# Encoder_Sheet3.net
KiCad netlist of a schematic drawn in Altium Designer
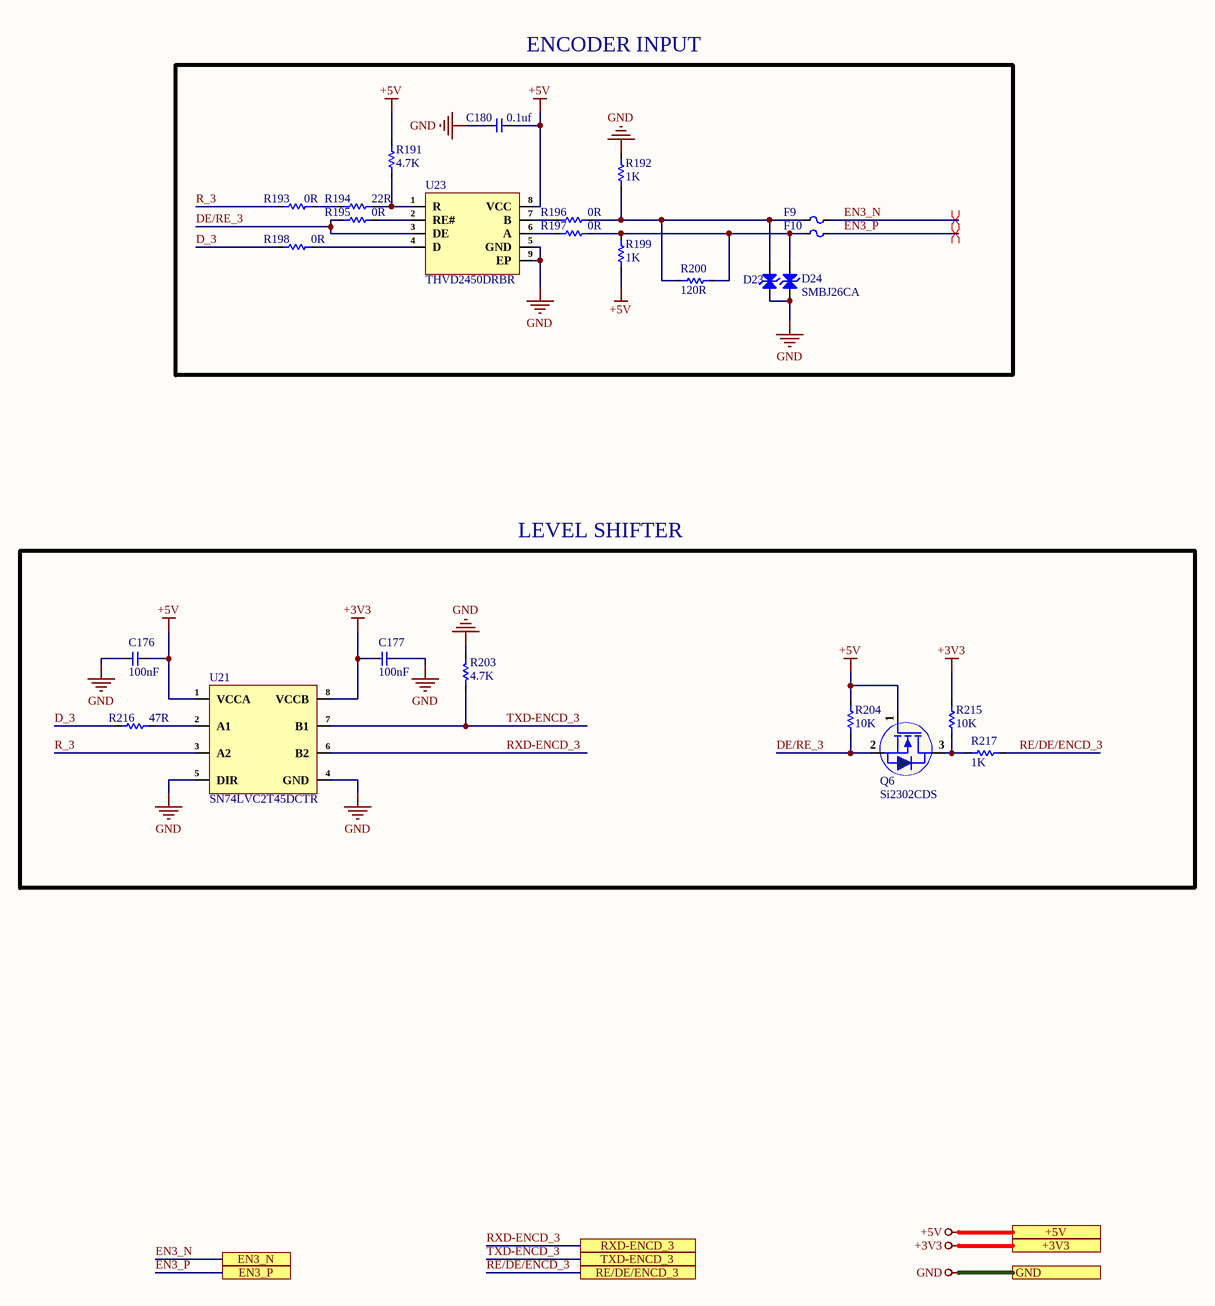
[diagram p0: Encoder_Sheet3.SchDoc]

(export (version "E")
  (design (tool "Eeschema 10.0.6"))
  (components
    (comp (ref "C176")
      (value "100nF")
      (footprint "cap-0402")
      (description "CAP CER 0.1UF 50V X7R 0402")
      (fields
        (field (name "MANUFACTURER") "TDK")
        (field (name "MANUFACTURER PART NUMBER") "C1005X7R1H104KT000F")
      )
      (libsource (lib "eSpark Libraries") (part "C1005X7R1H104KT000F"))
    )
    (comp (ref "C177")
      (value "100nF")
      (footprint "cap-0402")
      (description "CAP CER 0.1UF 50V X7R 0402")
      (fields
        (field (name "MANUFACTURER") "TDK")
        (field (name "MANUFACTURER PART NUMBER") "C1005X7R1H104KT000F")
      )
      (libsource (lib "eSpark Libraries") (part "C1005X7R1H104KT000F"))
    )
    (comp (ref "C180")
      (value "0.1uf")
      (footprint "Cap-0402")
      (description "CAP CER 0.1UF 100V X5R 0402")
      (fields
        (field (name "MANUFACTURER") "Murata")
        (field (name "MANUFACTURER PART NUMBER") "GRM155R62A104KE14D")
      )
      (libsource (lib "eSpark Libraries") (part "GRM155R62A104KE14D"))
    )
    (comp (ref "D23")
      (value "SMBJ26CA")
      (footprint "SMB Bi Directional")
      (description "SMB(DO-214AA) TVS ROHS")
      (fields (field (name "MANUFACTURER") "MSKSEMI") (field (name "LCSC PART NUMBER") "C5331111"))
      (libsource (lib "eSpark Libraries") (part "SMBJ26CA"))
    )
    (comp (ref "D24")
      (value "SMBJ26CA")
      (footprint "SMB Bi Directional")
      (description "SMB(DO-214AA) TVS ROHS")
      (fields (field (name "MANUFACTURER") "MSKSEMI") (field (name "LCSC PART NUMBER") "C5331111"))
      (libsource (lib "eSpark Libraries") (part "SMBJ26CA"))
    )
    (comp (ref "F9")
      (value "SMD0805P020TF")
      (footprint "Fuse-0805")
      (description "9V 200mA 100A 500mA 0805 Resettable Fuses ROHS")
      (fields (field (name "MANUFACTURER") "RUILON") (field (name "LCSC PART NUMBER") "C20976"))
      (libsource (lib "eSpark_centralized_Library(2022)") (part "SMD0805P020TF"))
    )
    (comp (ref "F10")
      (value "SMD0805P020TF")
      (footprint "Fuse-0805")
      (description "9V 200mA 100A 500mA 0805 Resettable Fuses ROHS")
      (fields (field (name "MANUFACTURER") "RUILON") (field (name "LCSC PART NUMBER") "C20976"))
      (libsource (lib "eSpark_centralized_Library(2022)") (part "SMD0805P020TF"))
    )
    (comp (ref "Q6")
      (value "Si2302CDS")
      (footprint "Sot-23")
      (description "N-CHANNEL 20-V (D-S) MOSFET")
      (fields
        (field (name "MANUFACTURER") "TECH PUBLIC")
        (field (name "MANUFACTURER PART NUMBER") "SI2302CDS")
      )
      (libsource (lib "eSpark_centralized_Library(2022)") (part "Si2302CDS"))
    )
    (comp (ref "R191")
      (value "4.7K")
      (footprint "Res-0402")
      (description "RES 4.7K OHM 1% 1/16W 0402")
      (fields
        (field (name "MANUFACTURER") "Yageo")
        (field (name "MANUFACTURER PART NUMBER") "RC0402FR-074K7L")
      )
      (libsource (lib "eSpark Libraries") (part "RC0402FR-074K7L"))
    )
    (comp (ref "R192")
      (value "1K")
      (footprint "Res-0402")
      (description "RES 1K OHM 1% 1/16W 0402")
      (fields
        (field (name "MANUFACTURER") "Yageo")
        (field (name "MANUFACTURER PART NUMBER") "RC0402FR-071KL")
      )
      (libsource (lib "eSpark Libraries") (part "RC0402FR-071KL"))
    )
    (comp (ref "R193")
      (value "0R")
      (footprint "Res-0603")
      (description "RES 0 OHM JUMPER 1/10W 0603")
      (fields
        (field (name "MANUFACTURER") "Yageo")
        (field (name "MANUFACTURER PART NUMBER") "RC0603JR-070RL")
      )
      (libsource (lib "eSpark Libraries") (part "RC0603JR-070RL"))
    )
    (comp (ref "R194")
      (value "22R")
      (footprint "Res-0402")
      (description "RES 22 OHM 1% 1/16W 0402")
      (fields
        (field (name "MANUFACTURER") "Yageo")
        (field (name "MANUFACTURER PART NUMBER") "RC0402FR-0722RL")
      )
      (libsource (lib "eSpark Libraries") (part "RC0402FR-0722RL"))
    )
    (comp (ref "R195")
      (value "0R")
      (footprint "Res-0603")
      (description "RES 0 OHM JUMPER 1/10W 0603")
      (fields
        (field (name "MANUFACTURER") "Yageo")
        (field (name "MANUFACTURER PART NUMBER") "RC0603JR-070RL")
      )
      (libsource (lib "eSpark Libraries") (part "RC0603JR-070RL"))
    )
    (comp (ref "R196")
      (value "0R")
      (footprint "Res-0603")
      (description "RES 0 OHM JUMPER 1/10W 0603")
      (fields
        (field (name "MANUFACTURER") "Yageo")
        (field (name "MANUFACTURER PART NUMBER") "RC0603JR-070RL")
      )
      (libsource (lib "eSpark Libraries") (part "RC0603JR-070RL"))
    )
    (comp (ref "R197")
      (value "0R")
      (footprint "Res-0603")
      (description "RES 0 OHM JUMPER 1/10W 0603")
      (fields
        (field (name "MANUFACTURER") "Yageo")
        (field (name "MANUFACTURER PART NUMBER") "RC0603JR-070RL")
      )
      (libsource (lib "eSpark Libraries") (part "RC0603JR-070RL"))
    )
    (comp (ref "R198")
      (value "0R")
      (footprint "Res-0603")
      (description "RES 0 OHM JUMPER 1/10W 0603")
      (fields
        (field (name "MANUFACTURER") "Yageo")
        (field (name "MANUFACTURER PART NUMBER") "RC0603JR-070RL")
      )
      (libsource (lib "eSpark Libraries") (part "RC0603JR-070RL"))
    )
    (comp (ref "R199")
      (value "1K")
      (footprint "Res-0402")
      (description "RES 1K OHM 1% 1/16W 0402")
      (fields
        (field (name "MANUFACTURER") "Yageo")
        (field (name "MANUFACTURER PART NUMBER") "RC0402FR-071KL")
      )
      (libsource (lib "eSpark Libraries") (part "RC0402FR-071KL"))
    )
    (comp (ref "R200")
      (value "120R")
      (footprint "Res-0402")
      (description "RES 120 OHM 1% 1/16W 0402")
      (fields
        (field (name "MANUFACTURER") "Yageo")
        (field (name "MANUFACTURER PART NUMBER") "RC0402FR-07120RL")
      )
      (libsource (lib "eSpark Libraries") (part "RC0402FR-07120RL"))
    )
    (comp (ref "R203")
      (value "4.7K")
      (footprint "Res-0402")
      (description "RES 4.7K OHM 1% 1/16W 0402")
      (fields
        (field (name "MANUFACTURER") "Yageo")
        (field (name "MANUFACTURER PART NUMBER") "RC0402FR-074K7L")
      )
      (libsource (lib "eSpark Libraries") (part "RC0402FR-074K7L"))
    )
    (comp (ref "R204")
      (value "10K")
      (footprint "Res-0402")
      (description "RES 10K OHM 1% 1/16W 0402")
      (fields
        (field (name "MANUFACTURER") "Yageo")
        (field (name "MANUFACTURER PART NUMBER") "RC0402FR-0710KL")
      )
      (libsource (lib "eSpark_centralized_Library(2022)") (part "RC0402FR-0710KL"))
    )
    (comp (ref "R215")
      (value "10K")
      (footprint "Res-0402")
      (description "RES 10K OHM 1% 1/16W 0402")
      (fields
        (field (name "MANUFACTURER") "Yageo")
        (field (name "MANUFACTURER PART NUMBER") "RC0402FR-0710KL")
      )
      (libsource (lib "eSpark_centralized_Library(2022)") (part "RC0402FR-0710KL"))
    )
    (comp (ref "R216")
      (value "47R")
      (footprint "Res-0402")
      (description "RES 47 OHM 1% 1/16W 0402")
      (fields
        (field (name "MANUFACTURER") "Yageo")
        (field (name "MANUFACTURER PART NUMBER") "RC0402FR-0747RL")
      )
      (libsource (lib "eSpark Libraries") (part "RC0402FR-0747RL"))
    )
    (comp (ref "R217")
      (value "1K")
      (footprint "Res-0603")
      (description "RES SMD 1K OHM 1% 1/10W 0603")
      (fields
        (field (name "MANUFACTURER") "Yageo")
        (field (name "MANUFACTURER PART NUMBER") "RC0603FR-071KL")
      )
      (libsource (lib "eSpark_centralized_Library(2022)") (part "RC0603FR-071KL"))
    )
    (comp (ref "U21")
      (value "SN74LVC2T45DCTR")
      (footprint "MSOP-8")
      (description "IC TRANSLATOR BIDIRECTIONAL SM8")
      (fields (field (name "LCSC PART NUMBER") "C22672") (field (name "MANUFACTURER") "Texas Instruments"))
      (libsource (lib "eSpark Libraries") (part "SN74LVC2T45DCTR"))
    )
    (comp (ref "U23")
      (value "THVD2450DRBR")
      (footprint "SON-8-EP(3x3)")
      (description "IC TRANSCEIVER HALF 1/1 8SON")
      (fields (field (name "MANUFACTURER") "Texas Instruments") (field (name "LCSC PART NUMBER") "C2878080"))
      (libsource (lib "eSpark Libraries") (part "THVD2450DRBR"))
    )
  )
  (nets
    (net (code "1") (name "+3V3") (class "Default")
      (node (ref "C177") (pin "1") (pinfunction "1_1") (pintype "passive"))
      (node (ref "R215") (pin "1") (pinfunction "1_1") (pintype "passive"))
      (node (ref "U21") (pin "8") (pinfunction "VCCB_8") (pintype "passive"))
    )
    (net (code "2") (name "+5V") (class "Default")
      (node (ref "C176") (pin "1") (pinfunction "1_1") (pintype "passive"))
      (node (ref "C180") (pin "2") (pinfunction "2_2") (pintype "passive"))
      (node (ref "Q6") (pin "1") (pinfunction "G_1") (pintype "passive"))
      (node (ref "R191") (pin "2") (pinfunction "2_2") (pintype "passive"))
      (node (ref "R199") (pin "1") (pinfunction "1_1") (pintype "passive"))
      (node (ref "R204") (pin "1") (pinfunction "1_1") (pintype "passive"))
      (node (ref "U21") (pin "1") (pinfunction "VCCA_1") (pintype "passive"))
      (node (ref "U23") (pin "8") (pinfunction "VCC_8") (pintype "passive"))
    )
    (net (code "3") (name "/DE{slash}RE_3") (class "Default")
      (node (ref "Q6") (pin "2") (pinfunction "S_2") (pintype "passive"))
      (node (ref "R195") (pin "1") (pinfunction "1_1") (pintype "passive"))
      (node (ref "R204") (pin "2") (pinfunction "2_2") (pintype "passive"))
      (node (ref "U23") (pin "3") (pinfunction "DE_3") (pintype "passive"))
    )
    (net (code "4") (name "/D_3") (class "Default")
      (node (ref "R198") (pin "1") (pinfunction "1_1") (pintype "passive"))
      (node (ref "R216") (pin "1") (pinfunction "1_1") (pintype "passive"))
    )
    (net (code "5") (name "/EN3_N") (class "Default")
      (node (ref "F9") (pin "2") (pinfunction "2_2") (pintype "passive"))
    )
    (net (code "6") (name "/EN3_P") (class "Default")
      (node (ref "F10") (pin "2") (pinfunction "2_2") (pintype "passive"))
    )
    (net (code "7") (name "/RE{slash}DE{slash}ENCD_3") (class "Default")
      (node (ref "R217") (pin "2") (pinfunction "2_2") (pintype "passive"))
    )
    (net (code "8") (name "/RXD-ENCD_3") (class "Default")
      (node (ref "U21") (pin "6") (pinfunction "B2_6") (pintype "passive"))
    )
    (net (code "9") (name "/R_3") (class "Default")
      (node (ref "R193") (pin "1") (pinfunction "1_1") (pintype "passive"))
      (node (ref "U21") (pin "3") (pinfunction "A2_3") (pintype "passive"))
    )
    (net (code "10") (name "/TXD-ENCD_3") (class "Default")
      (node (ref "R203") (pin "1") (pinfunction "1_1") (pintype "passive"))
      (node (ref "U21") (pin "7") (pinfunction "B1_7") (pintype "passive"))
    )
    (net (code "11") (name "GND") (class "Default")
      (node (ref "C176") (pin "2") (pinfunction "2_2") (pintype "passive"))
      (node (ref "C177") (pin "2") (pinfunction "2_2") (pintype "passive"))
      (node (ref "C180") (pin "1") (pinfunction "1_1") (pintype "passive"))
      (node (ref "D23") (pin "1") (pinfunction "A_1") (pintype "passive"))
      (node (ref "D24") (pin "1") (pinfunction "A_1") (pintype "passive"))
      (node (ref "R192") (pin "2") (pinfunction "2_2") (pintype "passive"))
      (node (ref "R203") (pin "2") (pinfunction "2_2") (pintype "passive"))
      (node (ref "U21") (pin "4") (pinfunction "GND_4") (pintype "passive"))
      (node (ref "U21") (pin "5") (pinfunction "DIR_5") (pintype "passive"))
      (node (ref "U23") (pin "5") (pinfunction "GND_5") (pintype "passive"))
      (node (ref "U23") (pin "9") (pinfunction "EP_9") (pintype "passive"))
    )
    (net (code "12") (name "Net-(D23-K)") (class "Default")
      (node (ref "D23") (pin "2") (pinfunction "K_2") (pintype "passive"))
      (node (ref "F9") (pin "1") (pinfunction "1_1") (pintype "passive"))
      (node (ref "R192") (pin "1") (pinfunction "1_1") (pintype "passive"))
      (node (ref "R196") (pin "2") (pinfunction "2_2") (pintype "passive"))
      (node (ref "R200") (pin "1") (pinfunction "1_1") (pintype "passive"))
    )
    (net (code "13") (name "Net-(D24-K)") (class "Default")
      (node (ref "D24") (pin "2") (pinfunction "K_2") (pintype "passive"))
      (node (ref "F10") (pin "1") (pinfunction "1_1") (pintype "passive"))
      (node (ref "R197") (pin "2") (pinfunction "2_2") (pintype "passive"))
      (node (ref "R199") (pin "2") (pinfunction "2_2") (pintype "passive"))
      (node (ref "R200") (pin "2") (pinfunction "2_2") (pintype "passive"))
    )
    (net (code "14") (name "Net-(Q6-D)") (class "Default")
      (node (ref "Q6") (pin "3") (pinfunction "D_3") (pintype "passive"))
      (node (ref "R215") (pin "2") (pinfunction "2_2") (pintype "passive"))
      (node (ref "R217") (pin "1") (pinfunction "1_1") (pintype "passive"))
    )
    (net (code "15") (name "Net-(R193-Pad2)") (class "Default")
      (node (ref "R193") (pin "2") (pinfunction "2_2") (pintype "passive"))
      (node (ref "R194") (pin "1") (pinfunction "1_1") (pintype "passive"))
    )
    (net (code "16") (name "Net-(U21-A1)") (class "Default")
      (node (ref "R216") (pin "2") (pinfunction "2_2") (pintype "passive"))
      (node (ref "U21") (pin "2") (pinfunction "A1_2") (pintype "passive"))
    )
    (net (code "17") (name "Net-(U23-A)") (class "Default")
      (node (ref "R197") (pin "1") (pinfunction "1_1") (pintype "passive"))
      (node (ref "U23") (pin "6") (pinfunction "A_6") (pintype "passive"))
    )
    (net (code "18") (name "Net-(U23-B)") (class "Default")
      (node (ref "R196") (pin "1") (pinfunction "1_1") (pintype "passive"))
      (node (ref "U23") (pin "7") (pinfunction "B_7") (pintype "passive"))
    )
    (net (code "19") (name "Net-(U23-D)") (class "Default")
      (node (ref "R198") (pin "2") (pinfunction "2_2") (pintype "passive"))
      (node (ref "U23") (pin "4") (pinfunction "D_4") (pintype "passive"))
    )
    (net (code "20") (name "Net-(U23-R)") (class "Default")
      (node (ref "R191") (pin "1") (pinfunction "1_1") (pintype "passive"))
      (node (ref "R194") (pin "2") (pinfunction "2_2") (pintype "passive"))
      (node (ref "U23") (pin "1") (pinfunction "R_1") (pintype "passive"))
    )
    (net (code "21") (name "Net-(U23-RE#)") (class "Default")
      (node (ref "R195") (pin "2") (pinfunction "2_2") (pintype "passive"))
      (node (ref "U23") (pin "2") (pinfunction "RE#_2") (pintype "passive"))
    )
  )
)
